# Sensorkort.net
KiCad netlist of a schematic drawn in Altium Designer
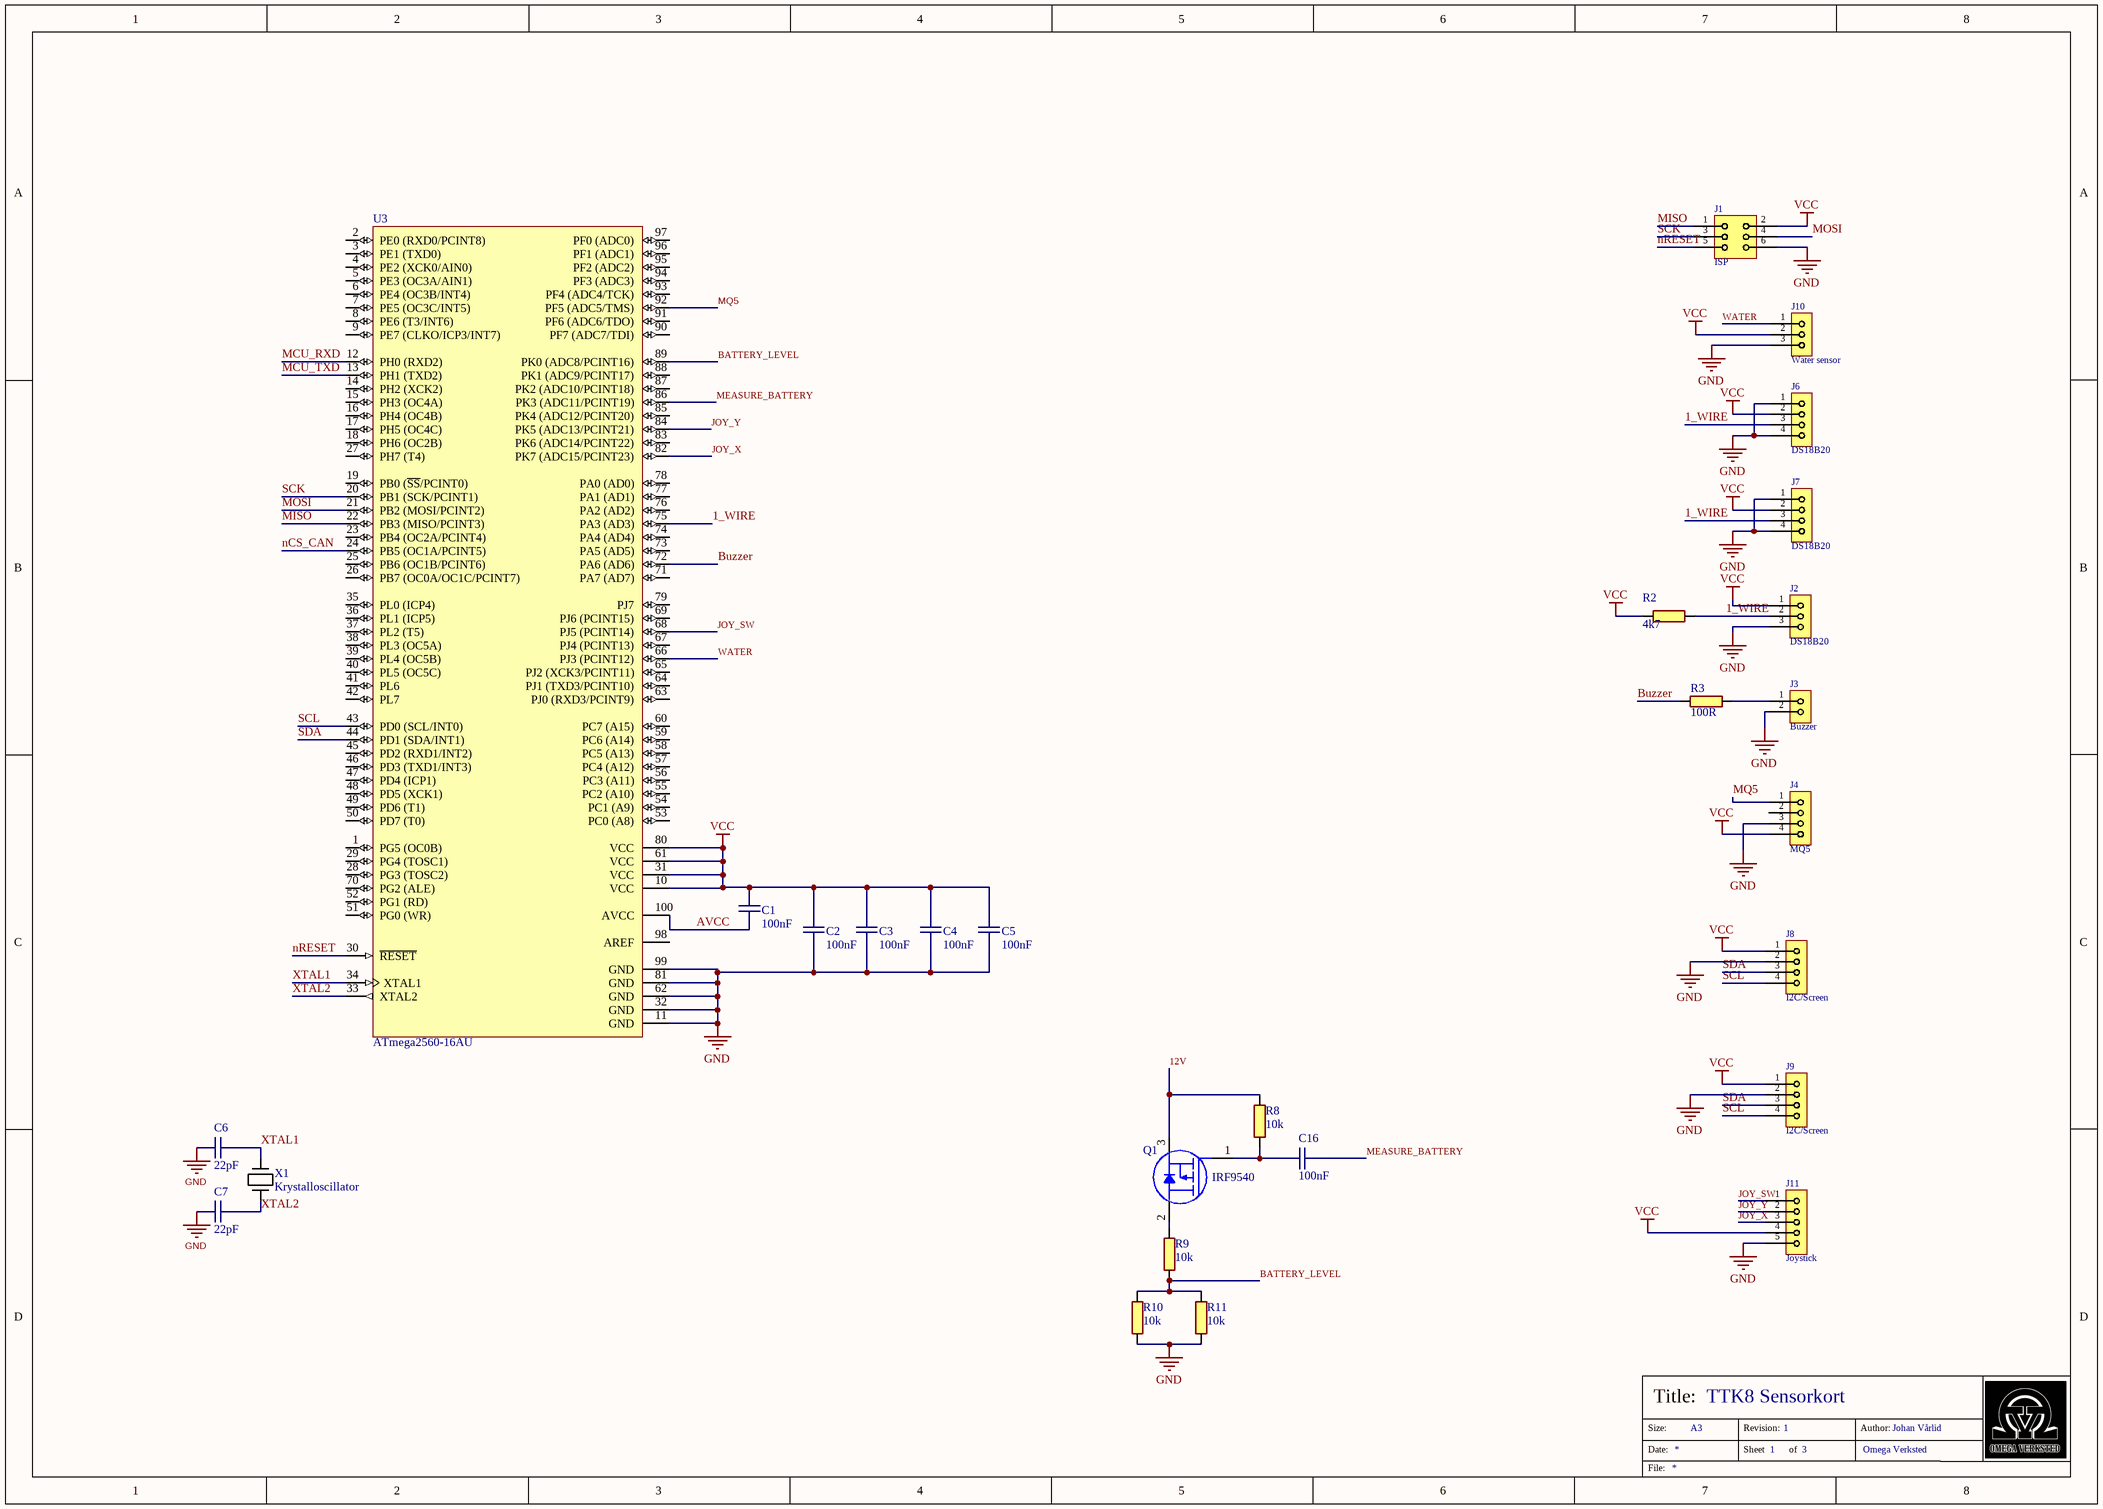
[diagram p0: Sensorkort.SchDoc]

(export (version "E")
  (design (tool "Eeschema 10.0.6"))
  (components
    (comp (ref "C1")
      (value "100nF")
      (footprint "CAPC0603(1608)55_N")
      (description "X7R 50V 5%")
      (libsource (lib "OVLib") (part "CAP"))
    )
    (comp (ref "C2")
      (value "100nF")
      (footprint "CAPC0603(1608)55_N")
      (description "X7R 50V 5%")
      (libsource (lib "OVLib") (part "CAP"))
    )
    (comp (ref "C3")
      (value "100nF")
      (footprint "CAPC0603(1608)55_N")
      (description "X7R 50V 5%")
      (libsource (lib "OVLib") (part "CAP"))
    )
    (comp (ref "C4")
      (value "100nF")
      (footprint "CAPC0603(1608)55_N")
      (description "X7R 50V 5%")
      (libsource (lib "OVLib") (part "CAP"))
    )
    (comp (ref "C5")
      (value "100nF")
      (footprint "CAPC0603(1608)55_N")
      (description "X7R 50V 5%")
      (libsource (lib "OVLib") (part "CAP"))
    )
    (comp (ref "C6")
      (value "22pF")
      (footprint "CAPC0603(1608)55_N")
      (description "Capacitor")
      (libsource (lib "OVLib") (part "CAP"))
    )
    (comp (ref "C7")
      (value "22pF")
      (footprint "CAPC0603(1608)55_N")
      (description "Capacitor")
      (libsource (lib "OVLib") (part "CAP"))
    )
    (comp (ref "C16")
      (value "100nF")
      (footprint "CAPC0603(1608)55_N")
      (description "X7R 50V 5%")
      (libsource (lib "OVLib") (part "CAP"))
    )
    (comp (ref "J1")
      (value "ISP")
      (footprint "HDRV6W64P254_2X3_762X508X900B")
      (libsource (lib "OVLib") (part "Header2x3"))
    )
    (comp (ref "J2")
      (value "DS18B20")
      (footprint "HDRV3W64P254_1X3_762X254X900B")
      (libsource (lib "OVLib") (part "Header1x3"))
    )
    (comp (ref "J3")
      (value "Buzzer")
      (footprint "HDRV2W64P254_1X2_508X254X900B")
      (libsource (lib "OVLib") (part "Header1x2"))
    )
    (comp (ref "J4")
      (value "MQ5")
      (footprint "HDRV4W64P254_1X4_1016X254X900B")
      (libsource (lib "OVLib") (part "Header1x4"))
    )
    (comp (ref "J6") (value "DS18B20") (footprint "CTB932HD_4") (libsource (lib "OVLib") (part "Header1x4")))
    (comp (ref "J7") (value "DS18B20") (footprint "CTB932HD_4") (libsource (lib "OVLib") (part "Header1x4")))
    (comp (ref "J8")
      (value "I2C/Screen")
      (footprint "HDRV4W64P254_1X4_1016X254X900B")
      (libsource (lib "OVLib") (part "Header1x4"))
    )
    (comp (ref "J9")
      (value "I2C/Screen")
      (footprint "HDRV4W64P254_1X4_1016X254X900B")
      (libsource (lib "OVLib") (part "Header1x4"))
    )
    (comp (ref "J10")
      (value "Water sensor")
      (footprint "HDRV3W64P254_1X3_762X254X900B")
      (libsource (lib "OVLib") (part "Header1x3"))
    )
    (comp (ref "J11")
      (value "Joystick")
      (footprint "HDRV5W64P254_1X5_1270X254X900B")
      (libsource (lib "OVLib") (part "Header1x5"))
    )
    (comp (ref "Q1")
      (value "IRF9540")
      (footprint "TO-220-3P")
      (description "MOSFET P-Kanal")
      (libsource (lib "OVLib") (part "MOSFET_P_GDS"))
    )
    (comp (ref "R2")
      (value "4k7")
      (footprint "RESC0603(1608)_N")
      (description "0.1W 1% Thick film resistor")
      (libsource (lib "") (part "Resistor2_1"))
    )
    (comp (ref "R3")
      (value "100R")
      (footprint "RESC0603(1608)_N")
      (description "0.1W 1% Thick film resistor")
      (libsource (lib "") (part "Resistor2_1"))
    )
    (comp (ref "R8")
      (value "10k")
      (footprint "RESC0603(1608)_N")
      (description "0.1W 1% Thick film resistor")
      (libsource (lib "OVLib") (part "Resistor2"))
    )
    (comp (ref "R9")
      (value "10k")
      (footprint "RESC0603(1608)_N")
      (description "0.1W 1% Thick film resistor")
      (libsource (lib "OVLib") (part "Resistor2"))
    )
    (comp (ref "R10")
      (value "10k")
      (footprint "RESC0603(1608)_N")
      (description "0.1W 1% Thick film resistor")
      (libsource (lib "OVLib") (part "Resistor2"))
    )
    (comp (ref "R11")
      (value "10k")
      (footprint "RESC0603(1608)_N")
      (description "0.1W 1% Thick film resistor")
      (libsource (lib "OVLib") (part "Resistor2"))
    )
    (comp (ref "U3")
      (value "ATmega2560-16AU")
      (footprint "100A_N")
      (fields (field (name "PUBLISHER") "Altium Limited"))
      (libsource (lib "Atmel Microcontroller 8-Bit megaAVR") (part "ATmega2560-16AU"))
    )
    (comp (ref "X1")
      (value "Krystalloscillator")
      (footprint "CrystalTH")
      (description "4MHz")
      (libsource (lib "OVLib") (part "GENERIC-CRYSTAL"))
    )
  )
  (nets
    (net (code "1") (name "/1_WIRE") (class "Default")
      (node (ref "J2") (pin "2") (pinfunction "2_2") (pintype "passive"))
      (node (ref "J6") (pin "3") (pinfunction "3_3") (pintype "passive"))
      (node (ref "J7") (pin "3") (pinfunction "3_3") (pintype "passive"))
      (node (ref "R2") (pin "2") (pinfunction "2_2") (pintype "passive"))
      (node (ref "U3") (pin "75") (pinfunction "PA3_(AD3)_75") (pintype "bidirectional"))
    )
    (net (code "2") (name "/12V") (class "Default")
      (node (ref "Q1") (pin "3") (pinfunction "Drain_3") (pintype "passive"))
      (node (ref "R8") (pin "2") (pinfunction "2_2") (pintype "passive"))
    )
    (net (code "3") (name "/AVCC") (class "Default")
      (node (ref "C1") (pin "2") (pinfunction "2_2") (pintype "passive"))
      (node (ref "U3") (pin "100") (pinfunction "AVCC_100") (pintype "power_in"))
    )
    (net (code "4") (name "/BATTERY_LEVEL") (class "Default")
      (node (ref "R10") (pin "2") (pinfunction "2_2") (pintype "passive"))
      (node (ref "R11") (pin "2") (pinfunction "2_2") (pintype "passive"))
      (node (ref "R9") (pin "1") (pinfunction "1_1") (pintype "passive"))
      (node (ref "U3") (pin "89") (pinfunction "PK0_(ADC8/PCINT16)_89") (pintype "bidirectional"))
    )
    (net (code "5") (name "/Buzzer") (class "Default")
      (node (ref "R3") (pin "1") (pinfunction "1_1") (pintype "passive"))
      (node (ref "U3") (pin "72") (pinfunction "PA6_(AD6)_72") (pintype "bidirectional"))
    )
    (net (code "6") (name "/JOY_SW") (class "Default")
      (node (ref "J11") (pin "1") (pinfunction "1_1") (pintype "passive"))
      (node (ref "U3") (pin "68") (pinfunction "PJ5_(PCINT14)_68") (pintype "bidirectional"))
    )
    (net (code "7") (name "/JOY_X") (class "Default")
      (node (ref "J11") (pin "3") (pinfunction "3_3") (pintype "passive"))
      (node (ref "U3") (pin "82") (pinfunction "PK7_(ADC15/PCINT23)_82") (pintype "bidirectional"))
    )
    (net (code "8") (name "/JOY_Y") (class "Default")
      (node (ref "J11") (pin "2") (pinfunction "2_2") (pintype "passive"))
      (node (ref "U3") (pin "84") (pinfunction "PK5_(ADC13/PCINT21)_84") (pintype "bidirectional"))
    )
    (net (code "9") (name "/MCU_RXD") (class "Default")
      (node (ref "U3") (pin "12") (pinfunction "PH0_(RXD2)_12") (pintype "bidirectional"))
    )
    (net (code "10") (name "/MCU_TXD") (class "Default")
      (node (ref "U3") (pin "13") (pinfunction "PH1_(TXD2)_13") (pintype "bidirectional"))
    )
    (net (code "11") (name "/MEASURE_BATTERY") (class "Default")
      (node (ref "C16") (pin "2") (pinfunction "2_2") (pintype "passive"))
      (node (ref "U3") (pin "86") (pinfunction "PK3_(ADC11/PCINT19)_86") (pintype "bidirectional"))
    )
    (net (code "12") (name "/MISO") (class "Default")
      (node (ref "J1") (pin "1") (pinfunction "1_1") (pintype "passive"))
      (node (ref "U3") (pin "22") (pinfunction "PB3_(MISO/PCINT3)_22") (pintype "bidirectional"))
    )
    (net (code "13") (name "/MOSI") (class "Default")
      (node (ref "J1") (pin "4") (pinfunction "4_4") (pintype "passive"))
      (node (ref "U3") (pin "21") (pinfunction "PB2_(MOSI/PCINT2)_21") (pintype "bidirectional"))
    )
    (net (code "14") (name "/MQ5") (class "Default")
      (node (ref "J4") (pin "1") (pinfunction "1_1") (pintype "passive"))
      (node (ref "U3") (pin "92") (pinfunction "PF5_(ADC5/TMS)_92") (pintype "bidirectional"))
    )
    (net (code "15") (name "/SCK") (class "Default")
      (node (ref "J1") (pin "3") (pinfunction "3_3") (pintype "passive"))
      (node (ref "U3") (pin "20") (pinfunction "PB1_(SCK/PCINT1)_20") (pintype "bidirectional"))
    )
    (net (code "16") (name "/SCL") (class "Default")
      (node (ref "J8") (pin "4") (pinfunction "4_4") (pintype "passive"))
      (node (ref "J9") (pin "4") (pinfunction "4_4") (pintype "passive"))
      (node (ref "U3") (pin "43") (pinfunction "PD0_(SCL/INT0)_43") (pintype "bidirectional"))
    )
    (net (code "17") (name "/SDA") (class "Default")
      (node (ref "J8") (pin "3") (pinfunction "3_3") (pintype "passive"))
      (node (ref "J9") (pin "3") (pinfunction "3_3") (pintype "passive"))
      (node (ref "U3") (pin "44") (pinfunction "PD1_(SDA/INT1)_44") (pintype "bidirectional"))
    )
    (net (code "18") (name "/WATER") (class "Default")
      (node (ref "J10") (pin "1") (pinfunction "1_1") (pintype "passive"))
      (node (ref "U3") (pin "66") (pinfunction "PJ3_(PCINT12)_66") (pintype "bidirectional"))
    )
    (net (code "19") (name "/XTAL1") (class "Default")
      (node (ref "C6") (pin "1") (pinfunction "1_1") (pintype "passive"))
      (node (ref "U3") (pin "34") (pinfunction "XTAL1_34") (pintype "input"))
      (node (ref "X1") (pin "1") (pintype "passive"))
    )
    (net (code "20") (name "/XTAL2") (class "Default")
      (node (ref "C7") (pin "2") (pinfunction "2_2") (pintype "passive"))
      (node (ref "U3") (pin "33") (pinfunction "XTAL2_33") (pintype "output"))
      (node (ref "X1") (pin "2") (pintype "passive"))
    )
    (net (code "21") (name "/nCS_CAN") (class "Default")
      (node (ref "U3") (pin "24") (pinfunction "PB5_(OC1A/PCINT5)_24") (pintype "bidirectional"))
    )
    (net (code "22") (name "/nRESET") (class "Default")
      (node (ref "J1") (pin "5") (pinfunction "5_5") (pintype "passive"))
      (node (ref "U3") (pin "30") (pinfunction "~{RESET}_30") (pintype "input"))
    )
    (net (code "23") (name "GND") (class "Default")
      (node (ref "C2") (pin "1") (pinfunction "1_1") (pintype "passive"))
      (node (ref "C3") (pin "1") (pinfunction "1_1") (pintype "passive"))
      (node (ref "C4") (pin "1") (pinfunction "1_1") (pintype "passive"))
      (node (ref "C5") (pin "1") (pinfunction "1_1") (pintype "passive"))
      (node (ref "C6") (pin "2") (pinfunction "2_2") (pintype "passive"))
      (node (ref "C7") (pin "1") (pinfunction "1_1") (pintype "passive"))
      (node (ref "J1") (pin "6") (pinfunction "6_6") (pintype "passive"))
      (node (ref "J10") (pin "3") (pinfunction "3_3") (pintype "passive"))
      (node (ref "J11") (pin "5") (pinfunction "5_5") (pintype "passive"))
      (node (ref "J2") (pin "3") (pinfunction "3_3") (pintype "passive"))
      (node (ref "J3") (pin "2") (pinfunction "2_2") (pintype "passive"))
      (node (ref "J4") (pin "3") (pinfunction "3_3") (pintype "passive"))
      (node (ref "J6") (pin "1") (pinfunction "1_1") (pintype "passive"))
      (node (ref "J6") (pin "4") (pinfunction "4_4") (pintype "passive"))
      (node (ref "J7") (pin "1") (pinfunction "1_1") (pintype "passive"))
      (node (ref "J7") (pin "4") (pinfunction "4_4") (pintype "passive"))
      (node (ref "J8") (pin "2") (pinfunction "2_2") (pintype "passive"))
      (node (ref "J9") (pin "2") (pinfunction "2_2") (pintype "passive"))
      (node (ref "R10") (pin "1") (pinfunction "1_1") (pintype "passive"))
      (node (ref "R11") (pin "1") (pinfunction "1_1") (pintype "passive"))
      (node (ref "U3") (pin "11") (pinfunction "GND_11") (pintype "power_in"))
      (node (ref "U3") (pin "32") (pinfunction "GND_32") (pintype "power_in"))
      (node (ref "U3") (pin "62") (pinfunction "GND_62") (pintype "power_in"))
      (node (ref "U3") (pin "81") (pinfunction "GND_81") (pintype "power_in"))
      (node (ref "U3") (pin "99") (pinfunction "GND_99") (pintype "power_in"))
    )
    (net (code "24") (name "Net-(J3-Pad1)") (class "Default")
      (node (ref "J3") (pin "1") (pinfunction "1_1") (pintype "passive"))
      (node (ref "R3") (pin "2") (pinfunction "2_2") (pintype "passive"))
    )
    (net (code "25") (name "Net-(Q1-Gate)") (class "Default")
      (node (ref "C16") (pin "1") (pinfunction "1_1") (pintype "passive"))
      (node (ref "Q1") (pin "1") (pinfunction "Gate_1") (pintype "passive"))
      (node (ref "R8") (pin "1") (pinfunction "1_1") (pintype "passive"))
    )
    (net (code "26") (name "Net-(Q1-Source)") (class "Default")
      (node (ref "Q1") (pin "2") (pinfunction "Source_2") (pintype "passive"))
      (node (ref "R9") (pin "2") (pinfunction "2_2") (pintype "passive"))
    )
    (net (code "27") (name "VCC") (class "Default")
      (node (ref "C1") (pin "1") (pinfunction "1_1") (pintype "passive"))
      (node (ref "C2") (pin "2") (pinfunction "2_2") (pintype "passive"))
      (node (ref "C3") (pin "2") (pinfunction "2_2") (pintype "passive"))
      (node (ref "C4") (pin "2") (pinfunction "2_2") (pintype "passive"))
      (node (ref "C5") (pin "2") (pinfunction "2_2") (pintype "passive"))
      (node (ref "J1") (pin "2") (pinfunction "2_2") (pintype "passive"))
      (node (ref "J10") (pin "2") (pinfunction "2_2") (pintype "passive"))
      (node (ref "J11") (pin "4") (pinfunction "4_4") (pintype "passive"))
      (node (ref "J2") (pin "1") (pinfunction "1_1") (pintype "passive"))
      (node (ref "J4") (pin "4") (pinfunction "4_4") (pintype "passive"))
      (node (ref "J6") (pin "2") (pinfunction "2_2") (pintype "passive"))
      (node (ref "J7") (pin "2") (pinfunction "2_2") (pintype "passive"))
      (node (ref "J8") (pin "1") (pinfunction "1_1") (pintype "passive"))
      (node (ref "J9") (pin "1") (pinfunction "1_1") (pintype "passive"))
      (node (ref "R2") (pin "1") (pinfunction "1_1") (pintype "passive"))
      (node (ref "U3") (pin "10") (pinfunction "VCC_10") (pintype "power_in"))
      (node (ref "U3") (pin "31") (pinfunction "VCC_31") (pintype "power_in"))
      (node (ref "U3") (pin "61") (pinfunction "VCC_61") (pintype "power_in"))
      (node (ref "U3") (pin "80") (pinfunction "VCC_80") (pintype "power_in"))
    )
    (net (code "28") (name "unconnected-(J4-Pad2)") (class "Default")
      (node (ref "J4") (pin "2") (pinfunction "2_2") (pintype "passive"))
    )
    (net (code "29") (name "unconnected-(U3-AREF-Pad98)") (class "Default")
      (node (ref "U3") (pin "98") (pinfunction "AREF_98") (pintype "power_in"))
    )
    (net (code "30") (name "unconnected-(U3-PA0_(AD0)-Pad78)") (class "Default")
      (node (ref "U3") (pin "78") (pinfunction "PA0_(AD0)_78") (pintype "bidirectional"))
    )
    (net (code "31") (name "unconnected-(U3-PA1_(AD1)-Pad77)") (class "Default")
      (node (ref "U3") (pin "77") (pinfunction "PA1_(AD1)_77") (pintype "bidirectional"))
    )
    (net (code "32") (name "unconnected-(U3-PA2_(AD2)-Pad76)") (class "Default")
      (node (ref "U3") (pin "76") (pinfunction "PA2_(AD2)_76") (pintype "bidirectional"))
    )
    (net (code "33") (name "unconnected-(U3-PA4_(AD4)-Pad74)") (class "Default")
      (node (ref "U3") (pin "74") (pinfunction "PA4_(AD4)_74") (pintype "bidirectional"))
    )
    (net (code "34") (name "unconnected-(U3-PA5_(AD5)-Pad73)") (class "Default")
      (node (ref "U3") (pin "73") (pinfunction "PA5_(AD5)_73") (pintype "bidirectional"))
    )
    (net (code "35") (name "unconnected-(U3-PA7_(AD7)-Pad71)") (class "Default")
      (node (ref "U3") (pin "71") (pinfunction "PA7_(AD7)_71") (pintype "bidirectional"))
    )
    (net (code "36") (name "unconnected-(U3-PB0_(~{SS}{slash}PCINT0)-Pad19)") (class "Default")
      (node (ref "U3") (pin "19") (pinfunction "PB0_(~{SS}/PCINT0)_19") (pintype "bidirectional"))
    )
    (net (code "37") (name "unconnected-(U3-PB4_(OC2A{slash}PCINT4)-Pad23)") (class "Default")
      (node (ref "U3") (pin "23") (pinfunction "PB4_(OC2A/PCINT4)_23") (pintype "bidirectional"))
    )
    (net (code "38") (name "unconnected-(U3-PB6_(OC1B{slash}PCINT6)-Pad25)") (class "Default")
      (node (ref "U3") (pin "25") (pinfunction "PB6_(OC1B/PCINT6)_25") (pintype "bidirectional"))
    )
    (net (code "39") (name "unconnected-(U3-PB7_(OC0A{slash}OC1C{slash}PCINT7)-Pad26)") (class "Default")
      (node (ref "U3") (pin "26") (pinfunction "PB7_(OC0A/OC1C/PCINT7)_26") (pintype "bidirectional"))
    )
    (net (code "40") (name "unconnected-(U3-PC0_(A8)-Pad53)") (class "Default")
      (node (ref "U3") (pin "53") (pinfunction "PC0_(A8)_53") (pintype "bidirectional"))
    )
    (net (code "41") (name "unconnected-(U3-PC1_(A9)-Pad54)") (class "Default")
      (node (ref "U3") (pin "54") (pinfunction "PC1_(A9)_54") (pintype "bidirectional"))
    )
    (net (code "42") (name "unconnected-(U3-PC2_(A10)-Pad55)") (class "Default")
      (node (ref "U3") (pin "55") (pinfunction "PC2_(A10)_55") (pintype "bidirectional"))
    )
    (net (code "43") (name "unconnected-(U3-PC3_(A11)-Pad56)") (class "Default")
      (node (ref "U3") (pin "56") (pinfunction "PC3_(A11)_56") (pintype "bidirectional"))
    )
    (net (code "44") (name "unconnected-(U3-PC4_(A12)-Pad57)") (class "Default")
      (node (ref "U3") (pin "57") (pinfunction "PC4_(A12)_57") (pintype "bidirectional"))
    )
    (net (code "45") (name "unconnected-(U3-PC5_(A13)-Pad58)") (class "Default")
      (node (ref "U3") (pin "58") (pinfunction "PC5_(A13)_58") (pintype "bidirectional"))
    )
    (net (code "46") (name "unconnected-(U3-PC6_(A14)-Pad59)") (class "Default")
      (node (ref "U3") (pin "59") (pinfunction "PC6_(A14)_59") (pintype "bidirectional"))
    )
    (net (code "47") (name "unconnected-(U3-PC7_(A15)-Pad60)") (class "Default")
      (node (ref "U3") (pin "60") (pinfunction "PC7_(A15)_60") (pintype "bidirectional"))
    )
    (net (code "48") (name "unconnected-(U3-PD2_(RXD1{slash}INT2)-Pad45)") (class "Default")
      (node (ref "U3") (pin "45") (pinfunction "PD2_(RXD1/INT2)_45") (pintype "bidirectional"))
    )
    (net (code "49") (name "unconnected-(U3-PD3_(TXD1{slash}INT3)-Pad46)") (class "Default")
      (node (ref "U3") (pin "46") (pinfunction "PD3_(TXD1/INT3)_46") (pintype "bidirectional"))
    )
    (net (code "50") (name "unconnected-(U3-PD4_(ICP1)-Pad47)") (class "Default")
      (node (ref "U3") (pin "47") (pinfunction "PD4_(ICP1)_47") (pintype "bidirectional"))
    )
    (net (code "51") (name "unconnected-(U3-PD5_(XCK1)-Pad48)") (class "Default")
      (node (ref "U3") (pin "48") (pinfunction "PD5_(XCK1)_48") (pintype "bidirectional"))
    )
    (net (code "52") (name "unconnected-(U3-PD6_(T1)-Pad49)") (class "Default")
      (node (ref "U3") (pin "49") (pinfunction "PD6_(T1)_49") (pintype "bidirectional"))
    )
    (net (code "53") (name "unconnected-(U3-PD7_(T0)-Pad50)") (class "Default")
      (node (ref "U3") (pin "50") (pinfunction "PD7_(T0)_50") (pintype "bidirectional"))
    )
    (net (code "54") (name "unconnected-(U3-PE0_(RXD0{slash}PCINT8)-Pad2)") (class "Default")
      (node (ref "U3") (pin "2") (pinfunction "PE0_(RXD0/PCINT8)_2") (pintype "bidirectional"))
    )
    (net (code "55") (name "unconnected-(U3-PE1_(TXD0)-Pad3)") (class "Default")
      (node (ref "U3") (pin "3") (pinfunction "PE1_(TXD0)_3") (pintype "bidirectional"))
    )
    (net (code "56") (name "unconnected-(U3-PE2_(XCK0{slash}AIN0)-Pad4)") (class "Default")
      (node (ref "U3") (pin "4") (pinfunction "PE2_(XCK0/AIN0)_4") (pintype "bidirectional"))
    )
    (net (code "57") (name "unconnected-(U3-PE3_(OC3A{slash}AIN1)-Pad5)") (class "Default")
      (node (ref "U3") (pin "5") (pinfunction "PE3_(OC3A/AIN1)_5") (pintype "bidirectional"))
    )
    (net (code "58") (name "unconnected-(U3-PE4_(OC3B{slash}INT4)-Pad6)") (class "Default")
      (node (ref "U3") (pin "6") (pinfunction "PE4_(OC3B/INT4)_6") (pintype "bidirectional"))
    )
    (net (code "59") (name "unconnected-(U3-PE5_(OC3C{slash}INT5)-Pad7)") (class "Default")
      (node (ref "U3") (pin "7") (pinfunction "PE5_(OC3C/INT5)_7") (pintype "bidirectional"))
    )
    (net (code "60") (name "unconnected-(U3-PE6_(T3{slash}INT6)-Pad8)") (class "Default")
      (node (ref "U3") (pin "8") (pinfunction "PE6_(T3/INT6)_8") (pintype "bidirectional"))
    )
    (net (code "61") (name "unconnected-(U3-PE7_(CLKO{slash}ICP3{slash}INT7)-Pad9)") (class "Default")
      (node (ref "U3") (pin "9") (pinfunction "PE7_(CLKO/ICP3/INT7)_9") (pintype "bidirectional"))
    )
    (net (code "62") (name "unconnected-(U3-PF0_(ADC0)-Pad97)") (class "Default")
      (node (ref "U3") (pin "97") (pinfunction "PF0_(ADC0)_97") (pintype "bidirectional"))
    )
    (net (code "63") (name "unconnected-(U3-PF1_(ADC1)-Pad96)") (class "Default")
      (node (ref "U3") (pin "96") (pinfunction "PF1_(ADC1)_96") (pintype "bidirectional"))
    )
    (net (code "64") (name "unconnected-(U3-PF2_(ADC2)-Pad95)") (class "Default")
      (node (ref "U3") (pin "95") (pinfunction "PF2_(ADC2)_95") (pintype "bidirectional"))
    )
    (net (code "65") (name "unconnected-(U3-PF3_(ADC3)-Pad94)") (class "Default")
      (node (ref "U3") (pin "94") (pinfunction "PF3_(ADC3)_94") (pintype "bidirectional"))
    )
    (net (code "66") (name "unconnected-(U3-PF4_(ADC4{slash}TCK)-Pad93)") (class "Default")
      (node (ref "U3") (pin "93") (pinfunction "PF4_(ADC4/TCK)_93") (pintype "bidirectional"))
    )
    (net (code "67") (name "unconnected-(U3-PF6_(ADC6{slash}TDO)-Pad91)") (class "Default")
      (node (ref "U3") (pin "91") (pinfunction "PF6_(ADC6/TDO)_91") (pintype "bidirectional"))
    )
    (net (code "68") (name "unconnected-(U3-PF7_(ADC7{slash}TDI)-Pad90)") (class "Default")
      (node (ref "U3") (pin "90") (pinfunction "PF7_(ADC7/TDI)_90") (pintype "bidirectional"))
    )
    (net (code "69") (name "unconnected-(U3-PG0_(WR)-Pad51)") (class "Default")
      (node (ref "U3") (pin "51") (pinfunction "PG0_(WR)_51") (pintype "bidirectional"))
    )
    (net (code "70") (name "unconnected-(U3-PG1_(RD)-Pad52)") (class "Default")
      (node (ref "U3") (pin "52") (pinfunction "PG1_(RD)_52") (pintype "bidirectional"))
    )
    (net (code "71") (name "unconnected-(U3-PG2_(ALE)-Pad70)") (class "Default")
      (node (ref "U3") (pin "70") (pinfunction "PG2_(ALE)_70") (pintype "bidirectional"))
    )
    (net (code "72") (name "unconnected-(U3-PG3_(TOSC2)-Pad28)") (class "Default")
      (node (ref "U3") (pin "28") (pinfunction "PG3_(TOSC2)_28") (pintype "bidirectional"))
    )
    (net (code "73") (name "unconnected-(U3-PG4_(TOSC1)-Pad29)") (class "Default")
      (node (ref "U3") (pin "29") (pinfunction "PG4_(TOSC1)_29") (pintype "bidirectional"))
    )
    (net (code "74") (name "unconnected-(U3-PG5_(OC0B)-Pad1)") (class "Default")
      (node (ref "U3") (pin "1") (pinfunction "PG5_(OC0B)_1") (pintype "bidirectional"))
    )
    (net (code "75") (name "unconnected-(U3-PH2_(XCK2)-Pad14)") (class "Default")
      (node (ref "U3") (pin "14") (pinfunction "PH2_(XCK2)_14") (pintype "bidirectional"))
    )
    (net (code "76") (name "unconnected-(U3-PH3_(OC4A)-Pad15)") (class "Default")
      (node (ref "U3") (pin "15") (pinfunction "PH3_(OC4A)_15") (pintype "bidirectional"))
    )
    (net (code "77") (name "unconnected-(U3-PH4_(OC4B)-Pad16)") (class "Default")
      (node (ref "U3") (pin "16") (pinfunction "PH4_(OC4B)_16") (pintype "bidirectional"))
    )
    (net (code "78") (name "unconnected-(U3-PH5_(OC4C)-Pad17)") (class "Default")
      (node (ref "U3") (pin "17") (pinfunction "PH5_(OC4C)_17") (pintype "bidirectional"))
    )
    (net (code "79") (name "unconnected-(U3-PH6_(OC2B)-Pad18)") (class "Default")
      (node (ref "U3") (pin "18") (pinfunction "PH6_(OC2B)_18") (pintype "bidirectional"))
    )
    (net (code "80") (name "unconnected-(U3-PH7_(T4)-Pad27)") (class "Default")
      (node (ref "U3") (pin "27") (pinfunction "PH7_(T4)_27") (pintype "bidirectional"))
    )
    (net (code "81") (name "unconnected-(U3-PJ0_(RXD3{slash}PCINT9)-Pad63)") (class "Default")
      (node (ref "U3") (pin "63") (pinfunction "PJ0_(RXD3/PCINT9)_63") (pintype "bidirectional"))
    )
    (net (code "82") (name "unconnected-(U3-PJ1_(TXD3{slash}PCINT10)-Pad64)") (class "Default")
      (node (ref "U3") (pin "64") (pinfunction "PJ1_(TXD3/PCINT10)_64") (pintype "bidirectional"))
    )
    (net (code "83") (name "unconnected-(U3-PJ2_(XCK3{slash}PCINT11)-Pad65)") (class "Default")
      (node (ref "U3") (pin "65") (pinfunction "PJ2_(XCK3/PCINT11)_65") (pintype "bidirectional"))
    )
    (net (code "84") (name "unconnected-(U3-PJ4_(PCINT13)-Pad67)") (class "Default")
      (node (ref "U3") (pin "67") (pinfunction "PJ4_(PCINT13)_67") (pintype "bidirectional"))
    )
    (net (code "85") (name "unconnected-(U3-PJ6_(PCINT15)-Pad69)") (class "Default")
      (node (ref "U3") (pin "69") (pinfunction "PJ6_(PCINT15)_69") (pintype "bidirectional"))
    )
    (net (code "86") (name "unconnected-(U3-PJ7-Pad79)") (class "Default")
      (node (ref "U3") (pin "79") (pinfunction "PJ7_79") (pintype "bidirectional"))
    )
    (net (code "87") (name "unconnected-(U3-PK1_(ADC9{slash}PCINT17)-Pad88)") (class "Default")
      (node (ref "U3") (pin "88") (pinfunction "PK1_(ADC9/PCINT17)_88") (pintype "bidirectional"))
    )
    (net (code "88") (name "unconnected-(U3-PK2_(ADC10{slash}PCINT18)-Pad87)") (class "Default")
      (node (ref "U3") (pin "87") (pinfunction "PK2_(ADC10/PCINT18)_87") (pintype "bidirectional"))
    )
    (net (code "89") (name "unconnected-(U3-PK4_(ADC12{slash}PCINT20)-Pad85)") (class "Default")
      (node (ref "U3") (pin "85") (pinfunction "PK4_(ADC12/PCINT20)_85") (pintype "bidirectional"))
    )
    (net (code "90") (name "unconnected-(U3-PK6_(ADC14{slash}PCINT22)-Pad83)") (class "Default")
      (node (ref "U3") (pin "83") (pinfunction "PK6_(ADC14/PCINT22)_83") (pintype "bidirectional"))
    )
    (net (code "91") (name "unconnected-(U3-PL0_(ICP4)-Pad35)") (class "Default")
      (node (ref "U3") (pin "35") (pinfunction "PL0_(ICP4)_35") (pintype "bidirectional"))
    )
    (net (code "92") (name "unconnected-(U3-PL1_(ICP5)-Pad36)") (class "Default")
      (node (ref "U3") (pin "36") (pinfunction "PL1_(ICP5)_36") (pintype "bidirectional"))
    )
    (net (code "93") (name "unconnected-(U3-PL2_(T5)-Pad37)") (class "Default")
      (node (ref "U3") (pin "37") (pinfunction "PL2_(T5)_37") (pintype "bidirectional"))
    )
    (net (code "94") (name "unconnected-(U3-PL3_(OC5A)-Pad38)") (class "Default")
      (node (ref "U3") (pin "38") (pinfunction "PL3_(OC5A)_38") (pintype "bidirectional"))
    )
    (net (code "95") (name "unconnected-(U3-PL4_(OC5B)-Pad39)") (class "Default")
      (node (ref "U3") (pin "39") (pinfunction "PL4_(OC5B)_39") (pintype "bidirectional"))
    )
    (net (code "96") (name "unconnected-(U3-PL5_(OC5C)-Pad40)") (class "Default")
      (node (ref "U3") (pin "40") (pinfunction "PL5_(OC5C)_40") (pintype "bidirectional"))
    )
    (net (code "97") (name "unconnected-(U3-PL6-Pad41)") (class "Default")
      (node (ref "U3") (pin "41") (pinfunction "PL6_41") (pintype "bidirectional"))
    )
    (net (code "98") (name "unconnected-(U3-PL7-Pad42)") (class "Default")
      (node (ref "U3") (pin "42") (pinfunction "PL7_42") (pintype "bidirectional"))
    )
  )
)
